# pc_ads1292r_brk.net
KiCad netlist of a schematic drawn in EAGLE
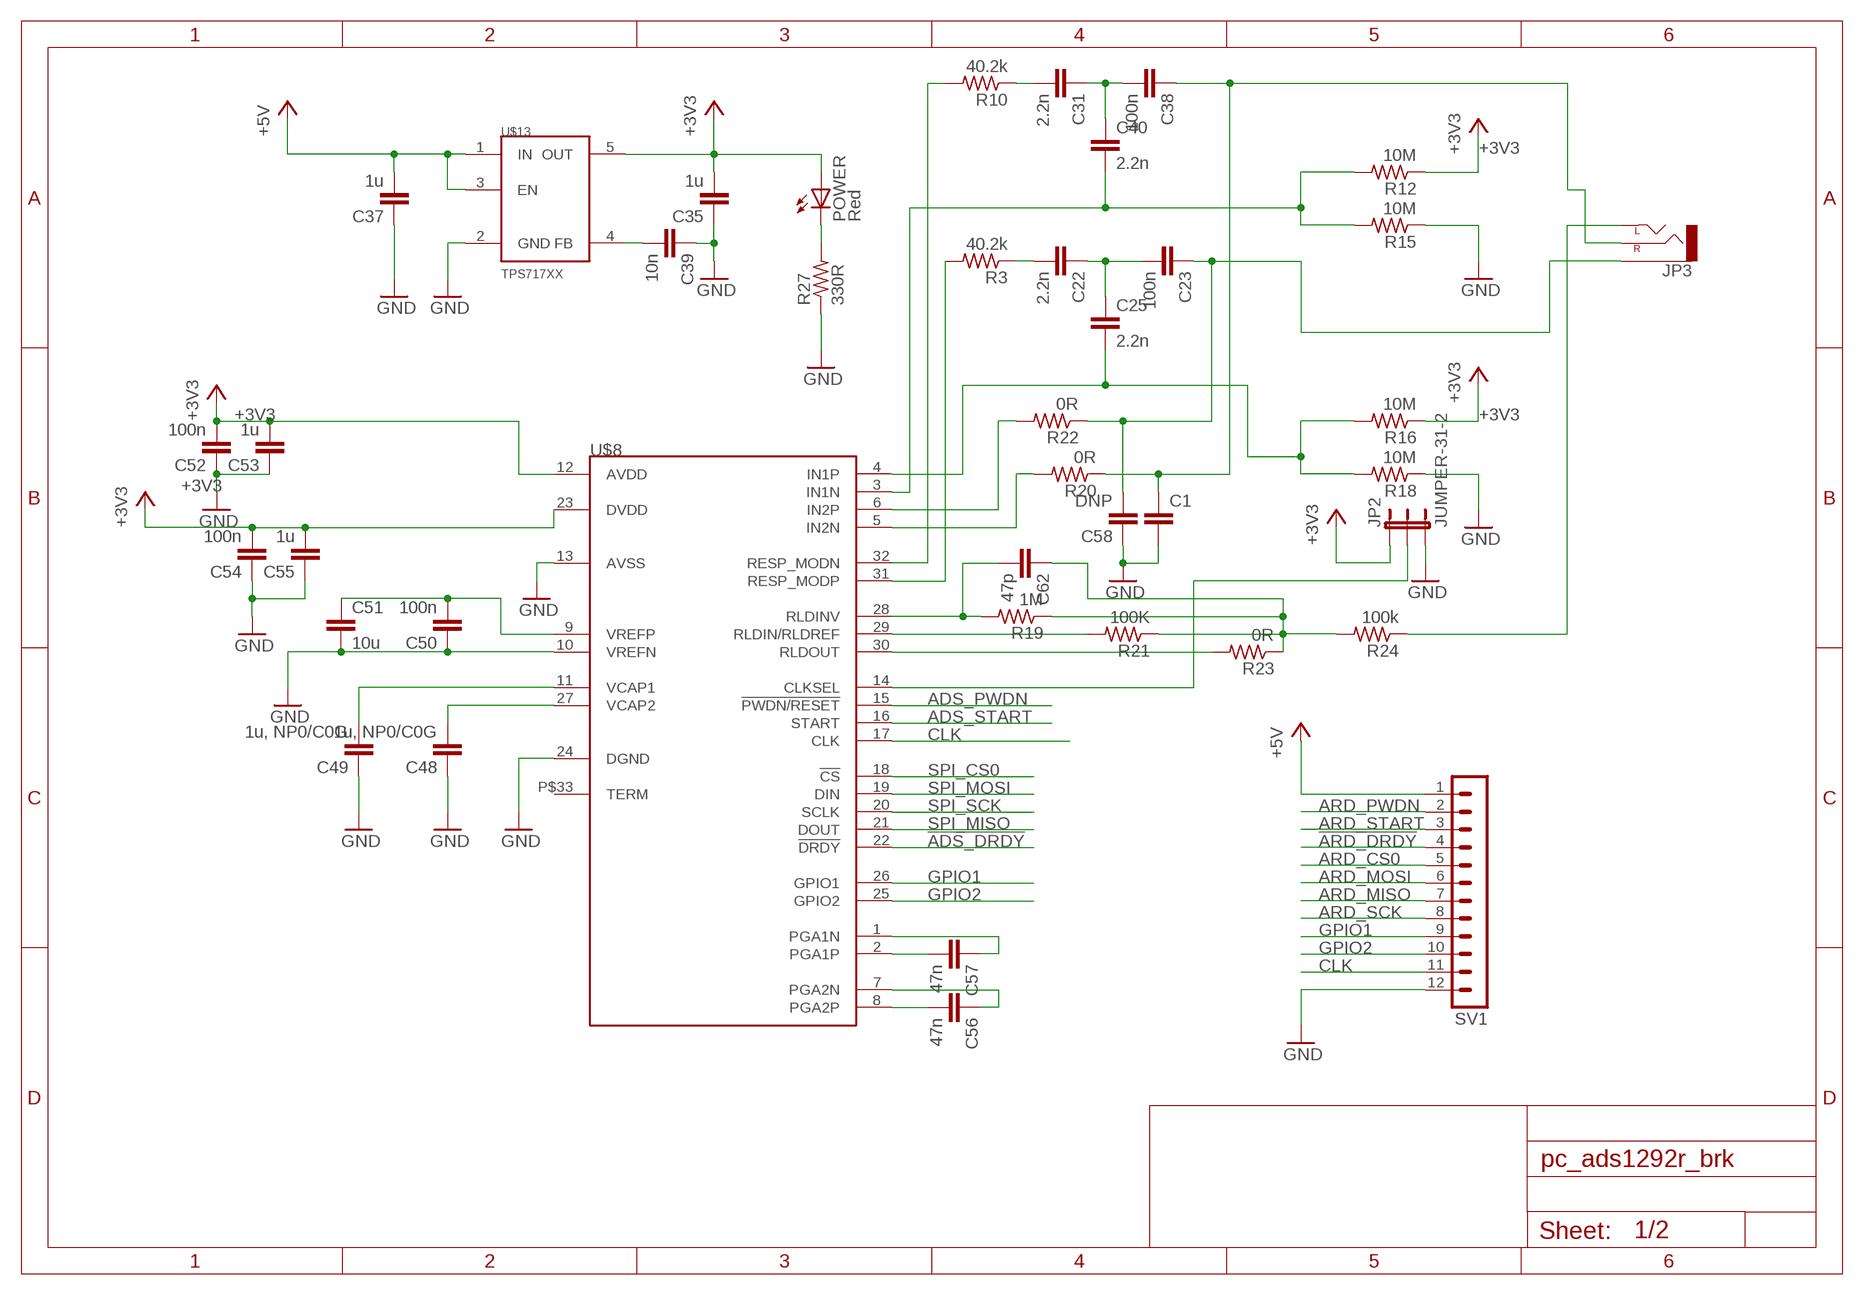
[diagram p0: schematic, sheet 1]
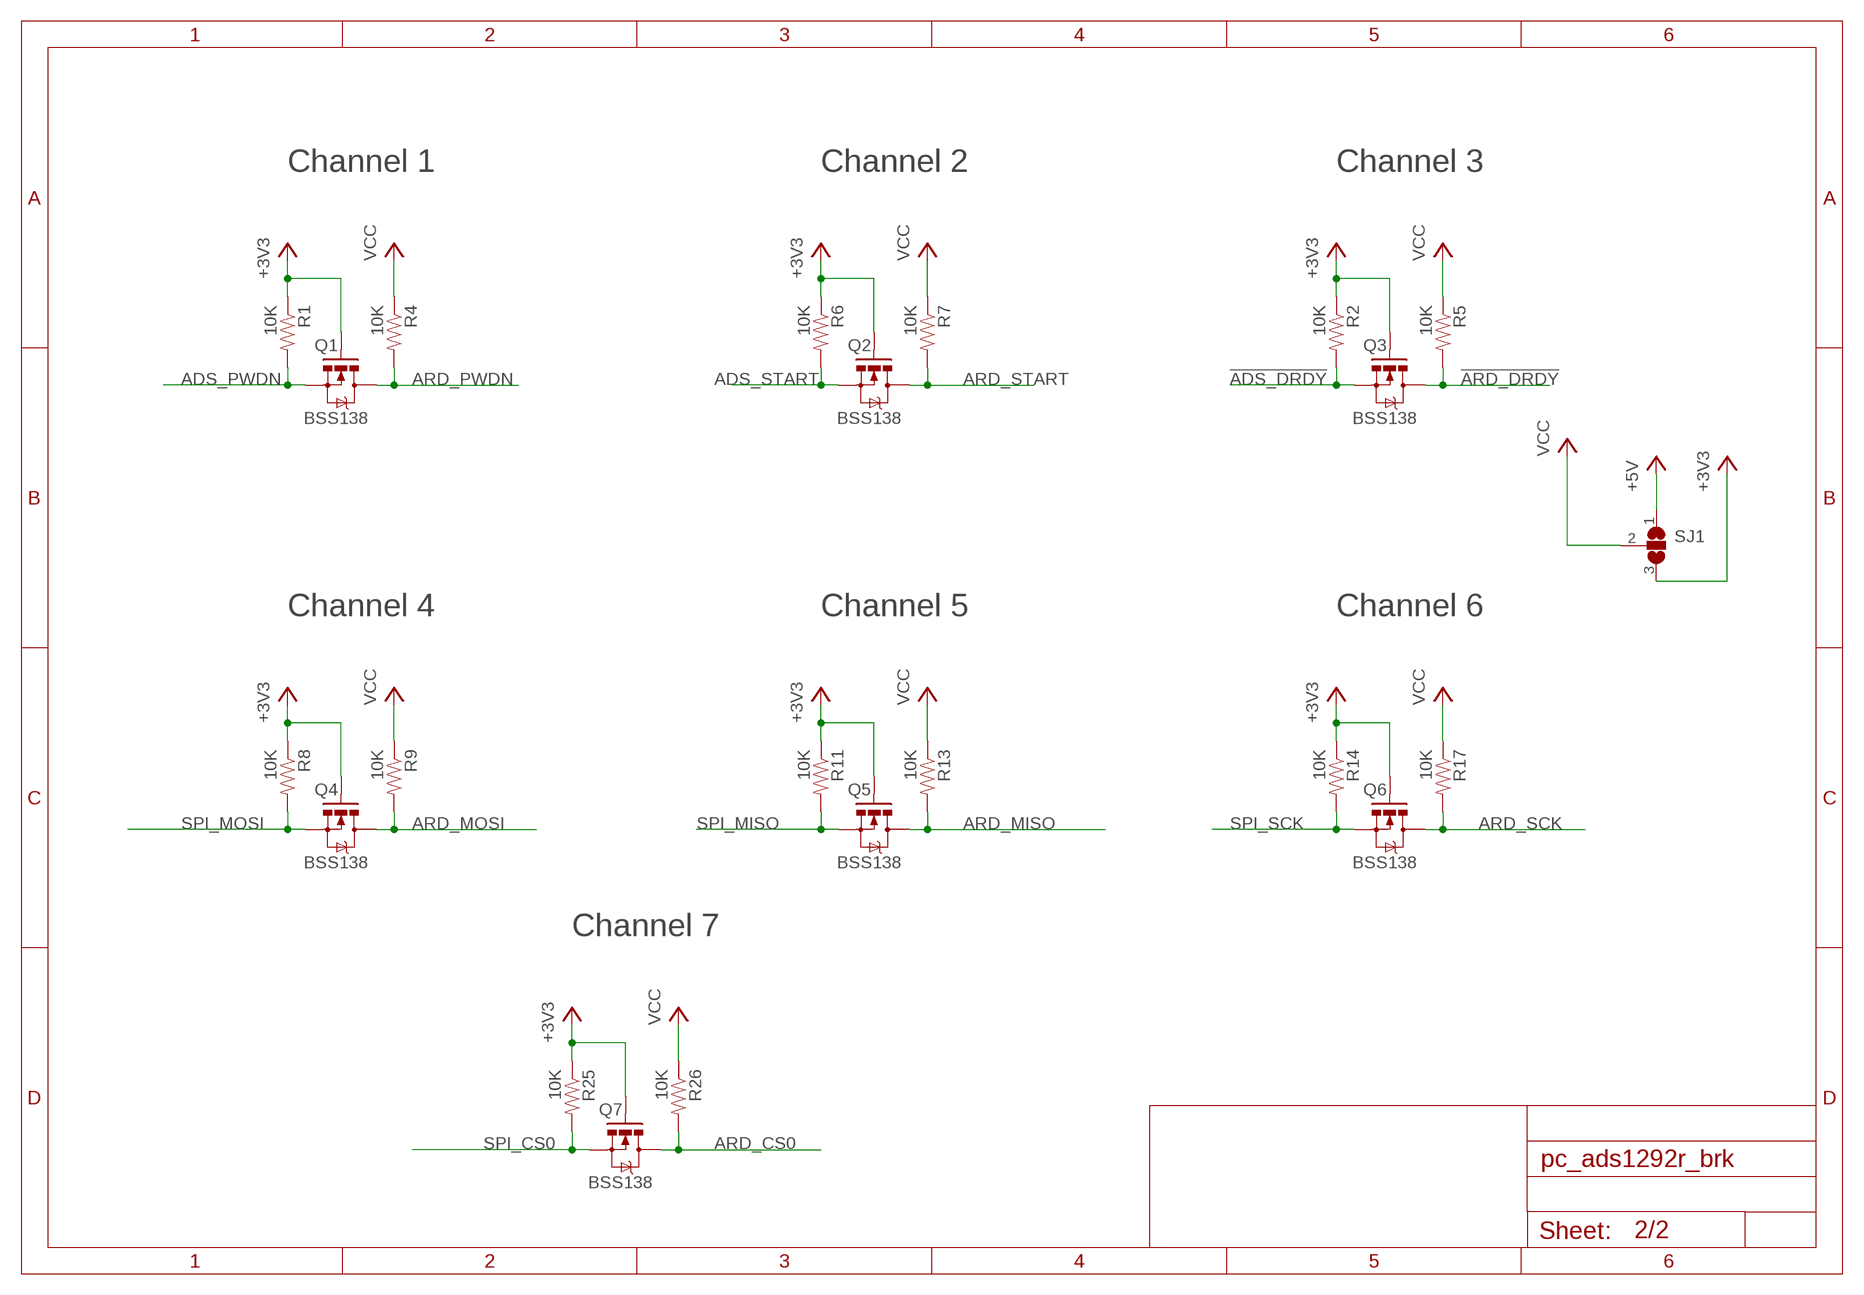
[diagram p1: schematic, sheet 2]

(export (version "E")
  (design (tool "Eeschema 10.0.6"))
  (components
    (comp (ref "C1")
      (value "C-EUC0402")
      (footprint "eagle-import:C0402")
      (libsource (lib "eagle-import") (part "C-EUC0402"))
    )
    (comp (ref "C22")
      (value "2.2n")
      (footprint "eagle-import:C0402")
      (libsource (lib "eagle-import") (part "C-EUC0402"))
    )
    (comp (ref "C23")
      (value "100n")
      (footprint "eagle-import:C0402")
      (libsource (lib "eagle-import") (part "C-EUC0402"))
    )
    (comp (ref "C25")
      (value "2.2n")
      (footprint "eagle-import:C0402")
      (libsource (lib "eagle-import") (part "C-EUC0402"))
    )
    (comp (ref "C31")
      (value "2.2n")
      (footprint "eagle-import:C0402")
      (libsource (lib "eagle-import") (part "C-EUC0402"))
    )
    (comp (ref "C35")
      (value "1u")
      (footprint "eagle-import:C0402")
      (libsource (lib "eagle-import") (part "C-EUC0402"))
    )
    (comp (ref "C37")
      (value "1u")
      (footprint "eagle-import:C0402")
      (libsource (lib "eagle-import") (part "C-EUC0402"))
    )
    (comp (ref "C38")
      (value "100n")
      (footprint "eagle-import:C0402")
      (libsource (lib "eagle-import") (part "C-EUC0402"))
    )
    (comp (ref "C39")
      (value "10n")
      (footprint "eagle-import:C0402")
      (libsource (lib "eagle-import") (part "C-EUC0402"))
    )
    (comp (ref "C40")
      (value "2.2n")
      (footprint "eagle-import:C0402")
      (libsource (lib "eagle-import") (part "C-EUC0402"))
    )
    (comp (ref "C48")
      (value "1u, NP0/C0G")
      (footprint "eagle-import:C0402")
      (libsource (lib "eagle-import") (part "C-EUC0402"))
    )
    (comp (ref "C49")
      (value "1u, NP0/C0G")
      (footprint "eagle-import:C0402")
      (libsource (lib "eagle-import") (part "C-EUC0402"))
    )
    (comp (ref "C50")
      (value "100n")
      (footprint "eagle-import:C0402")
      (libsource (lib "eagle-import") (part "C-EUC0402"))
    )
    (comp (ref "C51")
      (value "10u")
      (footprint "eagle-import:C0603")
      (libsource (lib "eagle-import") (part "resistor_C-EUC0603"))
    )
    (comp (ref "C52")
      (value "100n")
      (footprint "eagle-import:C0402")
      (libsource (lib "eagle-import") (part "C-EUC0402"))
    )
    (comp (ref "C53")
      (value "1u")
      (footprint "eagle-import:C0402")
      (libsource (lib "eagle-import") (part "C-EUC0402"))
    )
    (comp (ref "C54")
      (value "100n")
      (footprint "eagle-import:C0402")
      (libsource (lib "eagle-import") (part "C-EUC0402"))
    )
    (comp (ref "C55")
      (value "1u")
      (footprint "eagle-import:C0402")
      (libsource (lib "eagle-import") (part "C-EUC0402"))
    )
    (comp (ref "C56")
      (value "47n")
      (footprint "eagle-import:C0402")
      (libsource (lib "eagle-import") (part "C-EUC0402"))
    )
    (comp (ref "C57")
      (value "47n")
      (footprint "eagle-import:C0402")
      (libsource (lib "eagle-import") (part "C-EUC0402"))
    )
    (comp (ref "C58")
      (value "DNP")
      (footprint "eagle-import:C0402")
      (libsource (lib "eagle-import") (part "C-EUC0402"))
    )
    (comp (ref "C62")
      (value "47p")
      (footprint "eagle-import:C0402")
      (libsource (lib "eagle-import") (part "C-EUC0402"))
    )
    (comp (ref "JP2")
      (value "JUMPER-31-2")
      (footprint "eagle-import:SJ_3_PASTE1&2")
      (libsource (lib "eagle-import") (part "JUMPER-31-2"))
    )
    (comp (ref "JP3")
      (value "AUDIO-JACKSMD2")
      (footprint "eagle-import:AUDIO-JACK-3.5MM-SMD")
      (libsource (lib "eagle-import") (part "AUDIO-JACKSMD2"))
    )
    (comp (ref "POWER")
      (value "Red")
      (footprint "eagle-import:CHIPLED_0603")
      (libsource (lib "eagle-import") (part "LEDCHIPLED_0603"))
    )
    (comp (ref "R3")
      (value "40.2k")
      (footprint "eagle-import:R0402")
      (libsource (lib "eagle-import") (part "R-US_R0402"))
    )
    (comp (ref "R10")
      (value "40.2k")
      (footprint "eagle-import:R0402")
      (libsource (lib "eagle-import") (part "R-US_R0402"))
    )
    (comp (ref "R12")
      (value "10M")
      (footprint "eagle-import:R0402")
      (libsource (lib "eagle-import") (part "R-US_R0402"))
    )
    (comp (ref "R15")
      (value "10M")
      (footprint "eagle-import:R0402")
      (libsource (lib "eagle-import") (part "R-US_R0402"))
    )
    (comp (ref "R16")
      (value "10M")
      (footprint "eagle-import:R0402")
      (libsource (lib "eagle-import") (part "R-US_R0402"))
    )
    (comp (ref "R18")
      (value "10M")
      (footprint "eagle-import:R0402")
      (libsource (lib "eagle-import") (part "R-US_R0402"))
    )
    (comp (ref "R19")
      (value "1M")
      (footprint "eagle-import:R0402")
      (libsource (lib "eagle-import") (part "R-US_R0402"))
    )
    (comp (ref "R20")
      (value "0R")
      (footprint "eagle-import:R0402")
      (libsource (lib "eagle-import") (part "R-US_R0402"))
    )
    (comp (ref "R21")
      (value "100K")
      (footprint "eagle-import:R0402")
      (libsource (lib "eagle-import") (part "R-US_R0402"))
    )
    (comp (ref "R22")
      (value "0R")
      (footprint "eagle-import:R0402")
      (libsource (lib "eagle-import") (part "R-US_R0402"))
    )
    (comp (ref "R23")
      (value "0R")
      (footprint "eagle-import:R0402")
      (libsource (lib "eagle-import") (part "R-US_R0402"))
    )
    (comp (ref "R24")
      (value "100k")
      (footprint "eagle-import:R0402")
      (libsource (lib "eagle-import") (part "R-US_R0402"))
    )
    (comp (ref "R27")
      (value "330R")
      (footprint "eagle-import:R0402")
      (libsource (lib "eagle-import") (part "R-US_R0402"))
    )
    (comp (ref "SV1")
      (value "MA12-1")
      (footprint "eagle-import:MA12-1")
      (libsource (lib "eagle-import") (part "MA12-1"))
    )
    (comp (ref "U$8")
      (value "ADS1292RPVQFN32")
      (footprint "eagle-import:S-PVQFN-N32")
      (libsource (lib "eagle-import") (part "ADS1292RPVQFN32"))
    )
    (comp (ref "U$13")
      (value "TPS717XX")
      (footprint "eagle-import:SC70-5")
      (libsource (lib "eagle-import") (part "TPS717XX"))
    )
    (comp (ref "Q1")
      (value "BSS138")
      (footprint "eagle-import:SOT23-3")
      (libsource (lib "eagle-import") (part "MOSFET-NCHANNELSMD"))
    )
    (comp (ref "Q2")
      (value "BSS138")
      (footprint "eagle-import:SOT23-3")
      (libsource (lib "eagle-import") (part "MOSFET-NCHANNELSMD"))
    )
    (comp (ref "Q3")
      (value "BSS138")
      (footprint "eagle-import:SOT23-3")
      (libsource (lib "eagle-import") (part "MOSFET-NCHANNELSMD"))
    )
    (comp (ref "Q4")
      (value "BSS138")
      (footprint "eagle-import:SOT23-3")
      (libsource (lib "eagle-import") (part "MOSFET-NCHANNELSMD"))
    )
    (comp (ref "Q5")
      (value "BSS138")
      (footprint "eagle-import:SOT23-3")
      (libsource (lib "eagle-import") (part "MOSFET-NCHANNELSMD"))
    )
    (comp (ref "Q6")
      (value "BSS138")
      (footprint "eagle-import:SOT23-3")
      (libsource (lib "eagle-import") (part "MOSFET-NCHANNELSMD"))
    )
    (comp (ref "Q7")
      (value "BSS138")
      (footprint "eagle-import:SOT23-3")
      (libsource (lib "eagle-import") (part "MOSFET-NCHANNELSMD"))
    )
    (comp (ref "R1")
      (value "10K")
      (footprint "eagle-import:0603-RES")
      (libsource (lib "eagle-import") (part "RESISTOR0603-RES"))
    )
    (comp (ref "R2")
      (value "10K")
      (footprint "eagle-import:0603-RES")
      (libsource (lib "eagle-import") (part "RESISTOR0603-RES"))
    )
    (comp (ref "R4")
      (value "10K")
      (footprint "eagle-import:0603-RES")
      (libsource (lib "eagle-import") (part "RESISTOR0603-RES"))
    )
    (comp (ref "R5")
      (value "10K")
      (footprint "eagle-import:0603-RES")
      (libsource (lib "eagle-import") (part "RESISTOR0603-RES"))
    )
    (comp (ref "R6")
      (value "10K")
      (footprint "eagle-import:0603-RES")
      (libsource (lib "eagle-import") (part "RESISTOR0603-RES"))
    )
    (comp (ref "R7")
      (value "10K")
      (footprint "eagle-import:0603-RES")
      (libsource (lib "eagle-import") (part "RESISTOR0603-RES"))
    )
    (comp (ref "R8")
      (value "10K")
      (footprint "eagle-import:0603-RES")
      (libsource (lib "eagle-import") (part "RESISTOR0603-RES"))
    )
    (comp (ref "R9")
      (value "10K")
      (footprint "eagle-import:0603-RES")
      (libsource (lib "eagle-import") (part "RESISTOR0603-RES"))
    )
    (comp (ref "R11")
      (value "10K")
      (footprint "eagle-import:0603-RES")
      (libsource (lib "eagle-import") (part "RESISTOR0603-RES"))
    )
    (comp (ref "R13")
      (value "10K")
      (footprint "eagle-import:0603-RES")
      (libsource (lib "eagle-import") (part "RESISTOR0603-RES"))
    )
    (comp (ref "R14")
      (value "10K")
      (footprint "eagle-import:0603-RES")
      (libsource (lib "eagle-import") (part "RESISTOR0603-RES"))
    )
    (comp (ref "R17")
      (value "10K")
      (footprint "eagle-import:0603-RES")
      (libsource (lib "eagle-import") (part "RESISTOR0603-RES"))
    )
    (comp (ref "R25")
      (value "10K")
      (footprint "eagle-import:0603-RES")
      (libsource (lib "eagle-import") (part "RESISTOR0603-RES"))
    )
    (comp (ref "R26")
      (value "10K")
      (footprint "eagle-import:0603-RES")
      (libsource (lib "eagle-import") (part "RESISTOR0603-RES"))
    )
    (comp (ref "SJ1")
      (value "SJ2W")
      (footprint "eagle-import:SJ_2")
      (libsource (lib "eagle-import") (part "SJ2W"))
    )
  )
  (nets
    (net (code "1") (name "+3V3") (class "Default")
      (node (ref "C35") (pin "2") (pinfunction "2_2") (pintype "passive"))
      (node (ref "C52") (pin "2") (pinfunction "2_2") (pintype "passive"))
      (node (ref "C53") (pin "2") (pinfunction "2_2") (pintype "passive"))
      (node (ref "C54") (pin "2") (pinfunction "2_2") (pintype "passive"))
      (node (ref "C55") (pin "2") (pinfunction "2_2") (pintype "passive"))
      (node (ref "JP2") (pin "1") (pinfunction "1_1") (pintype "passive"))
      (node (ref "POWER") (pin "A") (pinfunction "A_A") (pintype "passive"))
      (node (ref "Q1") (pin "1") (pinfunction "G_1") (pintype "passive"))
      (node (ref "Q2") (pin "1") (pinfunction "G_1") (pintype "passive"))
      (node (ref "Q3") (pin "1") (pinfunction "G_1") (pintype "passive"))
      (node (ref "Q4") (pin "1") (pinfunction "G_1") (pintype "passive"))
      (node (ref "Q5") (pin "1") (pinfunction "G_1") (pintype "passive"))
      (node (ref "Q6") (pin "1") (pinfunction "G_1") (pintype "passive"))
      (node (ref "Q7") (pin "1") (pinfunction "G_1") (pintype "passive"))
      (node (ref "R1") (pin "1") (pinfunction "1_1") (pintype "passive"))
      (node (ref "R11") (pin "1") (pinfunction "1_1") (pintype "passive"))
      (node (ref "R12") (pin "1") (pinfunction "1_1") (pintype "passive"))
      (node (ref "R14") (pin "1") (pinfunction "1_1") (pintype "passive"))
      (node (ref "R16") (pin "1") (pinfunction "1_1") (pintype "passive"))
      (node (ref "R2") (pin "1") (pinfunction "1_1") (pintype "passive"))
      (node (ref "R25") (pin "1") (pinfunction "1_1") (pintype "passive"))
      (node (ref "R6") (pin "1") (pinfunction "1_1") (pintype "passive"))
      (node (ref "R8") (pin "1") (pinfunction "1_1") (pintype "passive"))
      (node (ref "SJ1") (pin "3") (pinfunction "3_3") (pintype "passive"))
      (node (ref "U$13") (pin "5") (pinfunction "OUT_5") (pintype "bidirectional"))
      (node (ref "U$8") (pin "12") (pinfunction "AVDD_12") (pintype "power_in"))
      (node (ref "U$8") (pin "23") (pinfunction "DVDD_23") (pintype "power_in"))
    )
    (net (code "2") (name "+5V") (class "Default")
      (node (ref "C37") (pin "2") (pinfunction "2_2") (pintype "passive"))
      (node (ref "SJ1") (pin "1") (pinfunction "1_1") (pintype "passive"))
      (node (ref "SV1") (pin "1") (pinfunction "1_1") (pintype "passive"))
      (node (ref "U$13") (pin "1") (pinfunction "IN_1") (pintype "bidirectional"))
      (node (ref "U$13") (pin "3") (pinfunction "EN_3") (pintype "bidirectional"))
    )
    (net (code "3") (name "ADS_PWDN") (class "Default")
      (node (ref "Q1") (pin "2") (pinfunction "S_2") (pintype "passive"))
      (node (ref "R1") (pin "2") (pinfunction "2_2") (pintype "passive"))
      (node (ref "U$8") (pin "15") (pinfunction "~{PWDN/RESET}_15") (pintype "bidirectional"))
    )
    (net (code "4") (name "ADS_START") (class "Default")
      (node (ref "Q2") (pin "2") (pinfunction "S_2") (pintype "passive"))
      (node (ref "R6") (pin "2") (pinfunction "2_2") (pintype "passive"))
      (node (ref "U$8") (pin "16") (pinfunction "START_16") (pintype "bidirectional"))
    )
    (net (code "5") (name "ARD_CS0") (class "Default")
      (node (ref "Q7") (pin "3") (pinfunction "D_3") (pintype "passive"))
      (node (ref "R26") (pin "2") (pinfunction "2_2") (pintype "passive"))
      (node (ref "SV1") (pin "5") (pinfunction "5_5") (pintype "passive"))
    )
    (net (code "6") (name "ARD_MISO") (class "Default")
      (node (ref "Q5") (pin "3") (pinfunction "D_3") (pintype "passive"))
      (node (ref "R13") (pin "2") (pinfunction "2_2") (pintype "passive"))
      (node (ref "SV1") (pin "7") (pinfunction "7_7") (pintype "passive"))
    )
    (net (code "7") (name "ARD_MOSI") (class "Default")
      (node (ref "Q4") (pin "3") (pinfunction "D_3") (pintype "passive"))
      (node (ref "R9") (pin "2") (pinfunction "2_2") (pintype "passive"))
      (node (ref "SV1") (pin "6") (pinfunction "6_6") (pintype "passive"))
    )
    (net (code "8") (name "ARD_PWDN") (class "Default")
      (node (ref "Q1") (pin "3") (pinfunction "D_3") (pintype "passive"))
      (node (ref "R4") (pin "2") (pinfunction "2_2") (pintype "passive"))
      (node (ref "SV1") (pin "2") (pinfunction "2_2") (pintype "passive"))
    )
    (net (code "9") (name "ARD_SCK") (class "Default")
      (node (ref "Q6") (pin "3") (pinfunction "D_3") (pintype "passive"))
      (node (ref "R17") (pin "2") (pinfunction "2_2") (pintype "passive"))
      (node (ref "SV1") (pin "8") (pinfunction "8_8") (pintype "passive"))
    )
    (net (code "10") (name "ARD_START") (class "Default")
      (node (ref "Q2") (pin "3") (pinfunction "D_3") (pintype "passive"))
      (node (ref "R7") (pin "2") (pinfunction "2_2") (pintype "passive"))
      (node (ref "SV1") (pin "3") (pinfunction "3_3") (pintype "passive"))
    )
    (net (code "11") (name "CLK") (class "Default")
      (node (ref "SV1") (pin "11") (pinfunction "11_11") (pintype "passive"))
      (node (ref "U$8") (pin "17") (pinfunction "CLK_17") (pintype "bidirectional"))
    )
    (net (code "12") (name "GND") (class "Default")
      (node (ref "C1") (pin "2") (pinfunction "2_2") (pintype "passive"))
      (node (ref "C35") (pin "1") (pinfunction "1_1") (pintype "passive"))
      (node (ref "C37") (pin "1") (pinfunction "1_1") (pintype "passive"))
      (node (ref "C39") (pin "1") (pinfunction "1_1") (pintype "passive"))
      (node (ref "C48") (pin "1") (pinfunction "1_1") (pintype "passive"))
      (node (ref "C49") (pin "1") (pinfunction "1_1") (pintype "passive"))
      (node (ref "C50") (pin "1") (pinfunction "1_1") (pintype "passive"))
      (node (ref "C51") (pin "2") (pinfunction "2_2") (pintype "passive"))
      (node (ref "C52") (pin "1") (pinfunction "1_1") (pintype "passive"))
      (node (ref "C53") (pin "1") (pinfunction "1_1") (pintype "passive"))
      (node (ref "C54") (pin "1") (pinfunction "1_1") (pintype "passive"))
      (node (ref "C55") (pin "1") (pinfunction "1_1") (pintype "passive"))
      (node (ref "C58") (pin "1") (pinfunction "1_1") (pintype "passive"))
      (node (ref "JP2") (pin "3") (pinfunction "3_3") (pintype "passive"))
      (node (ref "R15") (pin "1") (pinfunction "1_1") (pintype "passive"))
      (node (ref "R18") (pin "1") (pinfunction "1_1") (pintype "passive"))
      (node (ref "R27") (pin "1") (pinfunction "1_1") (pintype "passive"))
      (node (ref "SV1") (pin "12") (pinfunction "12_12") (pintype "passive"))
      (node (ref "U$13") (pin "2") (pinfunction "GND_2") (pintype "bidirectional"))
      (node (ref "U$8") (pin "10") (pinfunction "VREFN_10") (pintype "bidirectional"))
      (node (ref "U$8") (pin "13") (pinfunction "AVSS_13") (pintype "bidirectional"))
      (node (ref "U$8") (pin "24") (pinfunction "DGND_24") (pintype "bidirectional"))
    )
    (net (code "13") (name "GPIO1") (class "Default")
      (node (ref "SV1") (pin "9") (pinfunction "9_9") (pintype "passive"))
      (node (ref "U$8") (pin "26") (pinfunction "GPIO1_26") (pintype "bidirectional"))
    )
    (net (code "14") (name "GPIO2") (class "Default")
      (node (ref "SV1") (pin "10") (pinfunction "10_10") (pintype "passive"))
      (node (ref "U$8") (pin "25") (pinfunction "GPIO2_25") (pintype "bidirectional"))
    )
    (net (code "15") (name "Net-(C22-Pad1)") (class "Default")
      (node (ref "C22") (pin "1") (pinfunction "1_1") (pintype "passive"))
      (node (ref "C23") (pin "2") (pinfunction "2_2") (pintype "passive"))
      (node (ref "C25") (pin "1") (pinfunction "1_1") (pintype "passive"))
    )
    (net (code "16") (name "Net-(C22-Pad2)") (class "Default")
      (node (ref "C22") (pin "2") (pinfunction "2_2") (pintype "passive"))
      (node (ref "R3") (pin "1") (pinfunction "1_1") (pintype "passive"))
    )
    (net (code "17") (name "Net-(C23-Pad1)") (class "Default")
      (node (ref "C23") (pin "1") (pinfunction "1_1") (pintype "passive"))
      (node (ref "C58") (pin "2") (pinfunction "2_2") (pintype "passive"))
      (node (ref "JP3") (pin "SLEEVE") (pinfunction "SLEEVE_SLEEVE") (pintype "bidirectional"))
      (node (ref "R22") (pin "1") (pinfunction "1_1") (pintype "passive"))
    )
    (net (code "18") (name "Net-(C31-Pad1)") (class "Default")
      (node (ref "C31") (pin "1") (pinfunction "1_1") (pintype "passive"))
      (node (ref "C38") (pin "2") (pinfunction "2_2") (pintype "passive"))
      (node (ref "C40") (pin "1") (pinfunction "1_1") (pintype "passive"))
    )
    (net (code "19") (name "Net-(C31-Pad2)") (class "Default")
      (node (ref "C31") (pin "2") (pinfunction "2_2") (pintype "passive"))
      (node (ref "R10") (pin "1") (pinfunction "1_1") (pintype "passive"))
    )
    (net (code "20") (name "Net-(C62-Pad1)") (class "Default")
      (node (ref "C62") (pin "1") (pinfunction "1_1") (pintype "passive"))
      (node (ref "R19") (pin "1") (pinfunction "1_1") (pintype "passive"))
      (node (ref "R21") (pin "1") (pinfunction "1_1") (pintype "passive"))
      (node (ref "R23") (pin "1") (pinfunction "1_1") (pintype "passive"))
      (node (ref "R24") (pin "2") (pinfunction "2_2") (pintype "passive"))
    )
    (net (code "21") (name "Net-(JP3-LEFT)") (class "Default")
      (node (ref "JP3") (pin "TIP") (pinfunction "LEFT_TIP") (pintype "bidirectional"))
      (node (ref "R24") (pin "1") (pinfunction "1_1") (pintype "passive"))
    )
    (net (code "22") (name "Net-(JP3-RIGHT)") (class "Default")
      (node (ref "C1") (pin "1") (pinfunction "1_1") (pintype "passive"))
      (node (ref "C38") (pin "1") (pinfunction "1_1") (pintype "passive"))
      (node (ref "JP3") (pin "RING") (pinfunction "RIGHT_RING") (pintype "bidirectional"))
      (node (ref "R20") (pin "1") (pinfunction "1_1") (pintype "passive"))
    )
    (net (code "23") (name "Net-(POWER-PadC)") (class "Default")
      (node (ref "POWER") (pin "C") (pinfunction "C_C") (pintype "passive"))
      (node (ref "R27") (pin "2") (pinfunction "2_2") (pintype "passive"))
    )
    (net (code "24") (name "Net-(U$8-CLKSEL)") (class "Default")
      (node (ref "JP2") (pin "2") (pinfunction "2_2") (pintype "passive"))
      (node (ref "U$8") (pin "14") (pinfunction "CLKSEL_14") (pintype "bidirectional"))
    )
    (net (code "25") (name "Net-(U$8-IN1N)") (class "Default")
      (node (ref "C40") (pin "2") (pinfunction "2_2") (pintype "passive"))
      (node (ref "R12") (pin "2") (pinfunction "2_2") (pintype "passive"))
      (node (ref "R15") (pin "2") (pinfunction "2_2") (pintype "passive"))
      (node (ref "U$8") (pin "3") (pinfunction "IN1N_3") (pintype "input"))
    )
    (net (code "26") (name "Net-(U$8-IN1P)") (class "Default")
      (node (ref "C25") (pin "2") (pinfunction "2_2") (pintype "passive"))
      (node (ref "R16") (pin "2") (pinfunction "2_2") (pintype "passive"))
      (node (ref "R18") (pin "2") (pinfunction "2_2") (pintype "passive"))
      (node (ref "U$8") (pin "4") (pinfunction "IN1P_4") (pintype "input"))
    )
    (net (code "27") (name "Net-(U$8-IN2N)") (class "Default")
      (node (ref "R20") (pin "2") (pinfunction "2_2") (pintype "passive"))
      (node (ref "U$8") (pin "5") (pinfunction "IN2N_5") (pintype "input"))
    )
    (net (code "28") (name "Net-(U$8-IN2P)") (class "Default")
      (node (ref "R22") (pin "2") (pinfunction "2_2") (pintype "passive"))
      (node (ref "U$8") (pin "6") (pinfunction "IN2P_6") (pintype "input"))
    )
    (net (code "29") (name "Net-(U$8-PGA1N)") (class "Default")
      (node (ref "C57") (pin "1") (pinfunction "1_1") (pintype "passive"))
      (node (ref "U$8") (pin "1") (pinfunction "PGA1N_1") (pintype "bidirectional"))
    )
    (net (code "30") (name "Net-(U$8-PGA1P)") (class "Default")
      (node (ref "C57") (pin "2") (pinfunction "2_2") (pintype "passive"))
      (node (ref "U$8") (pin "2") (pinfunction "PGA1P_2") (pintype "bidirectional"))
    )
    (net (code "31") (name "Net-(U$8-PGA2N)") (class "Default")
      (node (ref "C56") (pin "1") (pinfunction "1_1") (pintype "passive"))
      (node (ref "U$8") (pin "7") (pinfunction "PGA2N_7") (pintype "bidirectional"))
    )
    (net (code "32") (name "Net-(U$8-PGA2P)") (class "Default")
      (node (ref "C56") (pin "2") (pinfunction "2_2") (pintype "passive"))
      (node (ref "U$8") (pin "8") (pinfunction "PGA2P_8") (pintype "bidirectional"))
    )
    (net (code "33") (name "Net-(U$8-RESP_MODN)") (class "Default")
      (node (ref "R10") (pin "2") (pinfunction "2_2") (pintype "passive"))
      (node (ref "U$8") (pin "32") (pinfunction "RESP_MODN_32") (pintype "bidirectional"))
    )
    (net (code "34") (name "Net-(U$8-RESP_MODP)") (class "Default")
      (node (ref "R3") (pin "2") (pinfunction "2_2") (pintype "passive"))
      (node (ref "U$8") (pin "31") (pinfunction "RESP_MODP_31") (pintype "bidirectional"))
    )
    (net (code "35") (name "Net-(U$8-RLDINV)") (class "Default")
      (node (ref "C62") (pin "2") (pinfunction "2_2") (pintype "passive"))
      (node (ref "R19") (pin "2") (pinfunction "2_2") (pintype "passive"))
      (node (ref "U$8") (pin "28") (pinfunction "RLDINV_28") (pintype "bidirectional"))
    )
    (net (code "36") (name "Net-(U$8-RLDIN{slash}RLDREF)") (class "Default")
      (node (ref "R21") (pin "2") (pinfunction "2_2") (pintype "passive"))
      (node (ref "U$8") (pin "29") (pinfunction "RLDIN/RLDREF_29") (pintype "bidirectional"))
    )
    (net (code "37") (name "Net-(U$8-RLDOUT)") (class "Default")
      (node (ref "R23") (pin "2") (pinfunction "2_2") (pintype "passive"))
      (node (ref "U$8") (pin "30") (pinfunction "RLDOUT_30") (pintype "bidirectional"))
    )
    (net (code "38") (name "Net-(U$8-VCAP1)") (class "Default")
      (node (ref "C49") (pin "2") (pinfunction "2_2") (pintype "passive"))
      (node (ref "U$8") (pin "11") (pinfunction "VCAP1_11") (pintype "bidirectional"))
    )
    (net (code "39") (name "Net-(U$8-VCAP2)") (class "Default")
      (node (ref "C48") (pin "2") (pinfunction "2_2") (pintype "passive"))
      (node (ref "U$8") (pin "27") (pinfunction "VCAP2_27") (pintype "bidirectional"))
    )
    (net (code "40") (name "Net-(U$8-VREFP)") (class "Default")
      (node (ref "C50") (pin "2") (pinfunction "2_2") (pintype "passive"))
      (node (ref "C51") (pin "1") (pinfunction "1_1") (pintype "passive"))
      (node (ref "U$8") (pin "9") (pinfunction "VREFP_9") (pintype "bidirectional"))
    )
    (net (code "41") (name "Net-(U$13-FB)") (class "Default")
      (node (ref "C39") (pin "2") (pinfunction "2_2") (pintype "passive"))
      (node (ref "U$13") (pin "4") (pinfunction "FB_4") (pintype "bidirectional"))
    )
    (net (code "42") (name "SPI_CS0") (class "Default")
      (node (ref "Q7") (pin "2") (pinfunction "S_2") (pintype "passive"))
      (node (ref "R25") (pin "2") (pinfunction "2_2") (pintype "passive"))
      (node (ref "U$8") (pin "18") (pinfunction "~{CS}_18") (pintype "bidirectional"))
    )
    (net (code "43") (name "SPI_MISO") (class "Default")
      (node (ref "Q5") (pin "2") (pinfunction "S_2") (pintype "passive"))
      (node (ref "R11") (pin "2") (pinfunction "2_2") (pintype "passive"))
      (node (ref "U$8") (pin "21") (pinfunction "DOUT_21") (pintype "bidirectional"))
    )
    (net (code "44") (name "SPI_MOSI") (class "Default")
      (node (ref "Q4") (pin "2") (pinfunction "S_2") (pintype "passive"))
      (node (ref "R8") (pin "2") (pinfunction "2_2") (pintype "passive"))
      (node (ref "U$8") (pin "19") (pinfunction "DIN_19") (pintype "bidirectional"))
    )
    (net (code "45") (name "SPI_SCK") (class "Default")
      (node (ref "Q6") (pin "2") (pinfunction "S_2") (pintype "passive"))
      (node (ref "R14") (pin "2") (pinfunction "2_2") (pintype "passive"))
      (node (ref "U$8") (pin "20") (pinfunction "SCLK_20") (pintype "bidirectional"))
    )
    (net (code "46") (name "VCC") (class "Default")
      (node (ref "R13") (pin "1") (pinfunction "1_1") (pintype "passive"))
      (node (ref "R17") (pin "1") (pinfunction "1_1") (pintype "passive"))
      (node (ref "R26") (pin "1") (pinfunction "1_1") (pintype "passive"))
      (node (ref "R4") (pin "1") (pinfunction "1_1") (pintype "passive"))
      (node (ref "R5") (pin "1") (pinfunction "1_1") (pintype "passive"))
      (node (ref "R7") (pin "1") (pinfunction "1_1") (pintype "passive"))
      (node (ref "R9") (pin "1") (pinfunction "1_1") (pintype "passive"))
      (node (ref "SJ1") (pin "2") (pinfunction "2_2") (pintype "passive"))
    )
    (net (code "47") (name "unconnected-(U$8-TERM-PadP$33)") (class "Default")
      (node (ref "U$8") (pin "P$33") (pinfunction "TERM_P$33") (pintype "bidirectional"))
    )
    (net (code "48") (name "~{ADS_DRDY}") (class "Default")
      (node (ref "Q3") (pin "2") (pinfunction "S_2") (pintype "passive"))
      (node (ref "R2") (pin "2") (pinfunction "2_2") (pintype "passive"))
      (node (ref "U$8") (pin "22") (pinfunction "~{DRDY}_22") (pintype "bidirectional"))
    )
    (net (code "49") (name "~{ARD_DRDY}") (class "Default")
      (node (ref "Q3") (pin "3") (pinfunction "D_3") (pintype "passive"))
      (node (ref "R5") (pin "2") (pinfunction "2_2") (pintype "passive"))
      (node (ref "SV1") (pin "4") (pinfunction "4_4") (pintype "passive"))
    )
  )
)
